# Solar_5_cell_V4_fixed_footprint.net
KiCad netlist of a schematic drawn in EAGLE
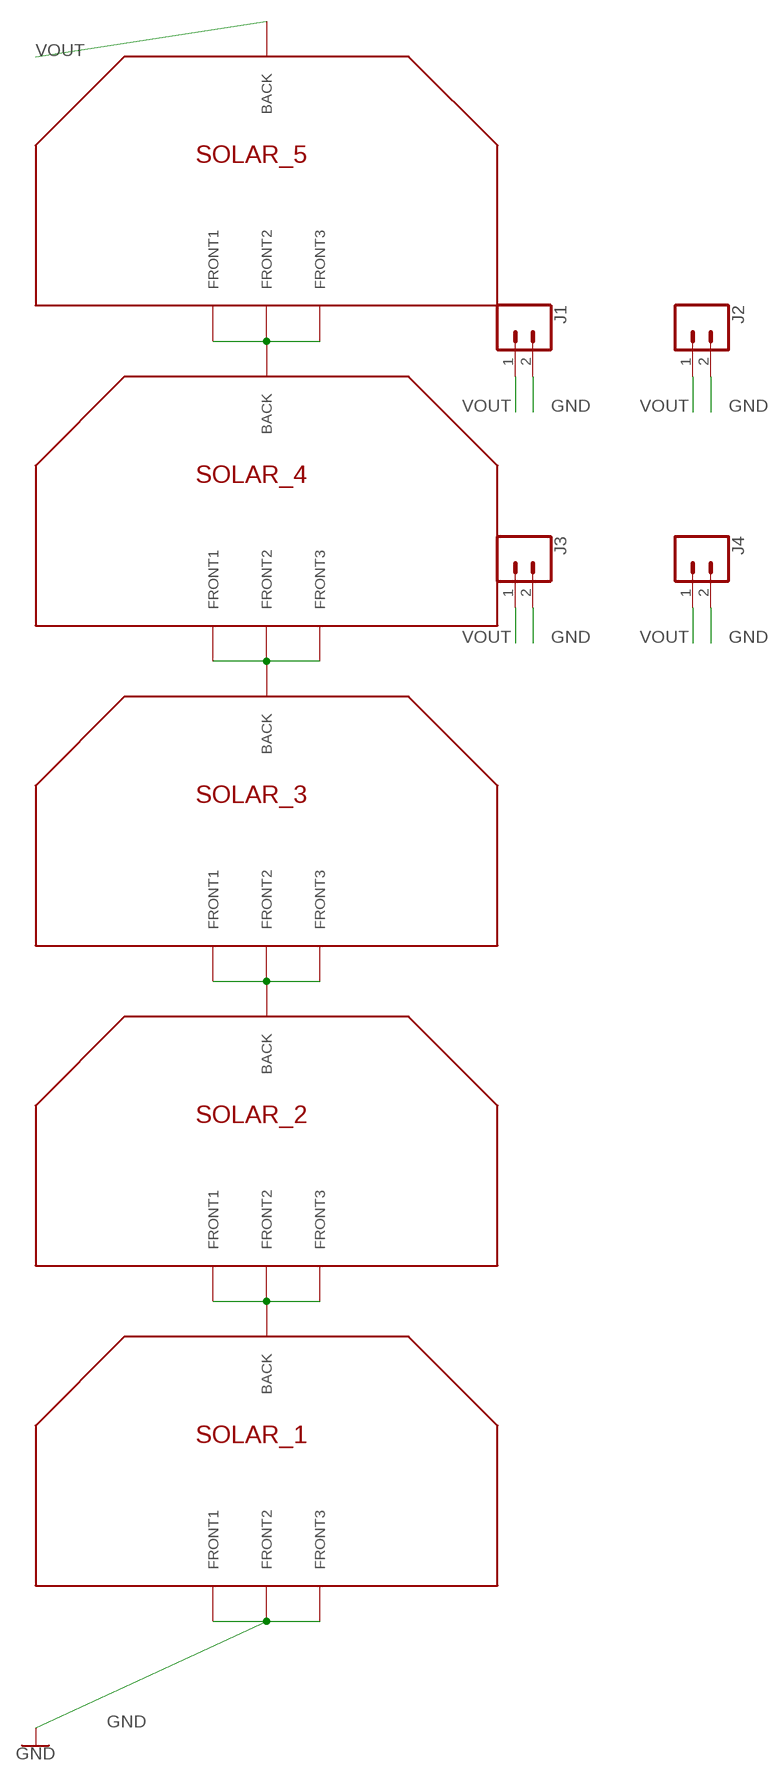
[diagram p0: schematic, sheet 1]

(export (version "E")
  (design (tool "Eeschema 10.0.6"))
  (components
    (comp (ref "J1")
      (value "CONN_02")
      (footprint "eagle-import:1X02")
      (libsource (lib "eagle-import") (part "CONN_02"))
    )
    (comp (ref "J2")
      (value "CONN_02")
      (footprint "eagle-import:1X02")
      (libsource (lib "eagle-import") (part "CONN_02"))
    )
    (comp (ref "J3")
      (value "CONN_02")
      (footprint "eagle-import:1X02")
      (libsource (lib "eagle-import") (part "CONN_02"))
    )
    (comp (ref "J4")
      (value "CONN_02")
      (footprint "eagle-import:1X02")
      (libsource (lib "eagle-import") (part "CONN_02"))
    )
    (comp (ref "SOLAR_1")
      (value "SOLAR_CELL_HALF_TABSFULL_TABS")
      (footprint "eagle-import:SOLAR_CELL_3G30A_FULL_TABS")
      (libsource (lib "eagle-import") (part "SOLAR_CELL_HALF_TABSFULL_TABS"))
    )
    (comp (ref "SOLAR_2")
      (value "SOLAR_CELL_HALF_TABSFULL_TABS")
      (footprint "eagle-import:SOLAR_CELL_3G30A_FULL_TABS")
      (libsource (lib "eagle-import") (part "SOLAR_CELL_HALF_TABSFULL_TABS"))
    )
    (comp (ref "SOLAR_3")
      (value "SOLAR_CELL_HALF_TABSFULL_TABS")
      (footprint "eagle-import:SOLAR_CELL_3G30A_FULL_TABS")
      (libsource (lib "eagle-import") (part "SOLAR_CELL_HALF_TABSFULL_TABS"))
    )
    (comp (ref "SOLAR_4")
      (value "SOLAR_CELL_HALF_TABSFULL_TABS")
      (footprint "eagle-import:SOLAR_CELL_3G30A_FULL_TABS")
      (libsource (lib "eagle-import") (part "SOLAR_CELL_HALF_TABSFULL_TABS"))
    )
    (comp (ref "SOLAR_5")
      (value "SOLAR_CELL_HALF_TABSFULL_TABS")
      (footprint "eagle-import:SOLAR_CELL_3G30A_FULL_TABS")
      (libsource (lib "eagle-import") (part "SOLAR_CELL_HALF_TABSFULL_TABS"))
    )
  )
  (nets
    (net (code "1") (name "/VOUT") (class "Default")
      (node (ref "J1") (pin "1") (pinfunction "1_1") (pintype "passive"))
      (node (ref "J2") (pin "1") (pinfunction "1_1") (pintype "passive"))
      (node (ref "J3") (pin "1") (pinfunction "1_1") (pintype "passive"))
      (node (ref "J4") (pin "1") (pinfunction "1_1") (pintype "passive"))
      (node (ref "SOLAR_5") (pin "P$1") (pinfunction "BACK_P$1") (pintype "bidirectional"))
    )
    (net (code "2") (name "GND") (class "Default")
      (node (ref "J1") (pin "2") (pinfunction "2_2") (pintype "passive"))
      (node (ref "J2") (pin "2") (pinfunction "2_2") (pintype "passive"))
      (node (ref "J3") (pin "2") (pinfunction "2_2") (pintype "passive"))
      (node (ref "J4") (pin "2") (pinfunction "2_2") (pintype "passive"))
      (node (ref "SOLAR_1") (pin "P$F1") (pinfunction "FRONT1_P$F1") (pintype "bidirectional"))
      (node (ref "SOLAR_1") (pin "P$F2") (pinfunction "FRONT2_P$F2") (pintype "bidirectional"))
      (node (ref "SOLAR_1") (pin "P$F3") (pinfunction "FRONT3_P$F3") (pintype "bidirectional"))
    )
    (net (code "3") (name "Net-(SOLAR_1-BACK)") (class "Default")
      (node (ref "SOLAR_1") (pin "P$1") (pinfunction "BACK_P$1") (pintype "bidirectional"))
      (node (ref "SOLAR_2") (pin "P$F1") (pinfunction "FRONT1_P$F1") (pintype "bidirectional"))
      (node (ref "SOLAR_2") (pin "P$F2") (pinfunction "FRONT2_P$F2") (pintype "bidirectional"))
      (node (ref "SOLAR_2") (pin "P$F3") (pinfunction "FRONT3_P$F3") (pintype "bidirectional"))
    )
    (net (code "4") (name "Net-(SOLAR_2-BACK)") (class "Default")
      (node (ref "SOLAR_2") (pin "P$1") (pinfunction "BACK_P$1") (pintype "bidirectional"))
      (node (ref "SOLAR_3") (pin "P$F1") (pinfunction "FRONT1_P$F1") (pintype "bidirectional"))
      (node (ref "SOLAR_3") (pin "P$F2") (pinfunction "FRONT2_P$F2") (pintype "bidirectional"))
      (node (ref "SOLAR_3") (pin "P$F3") (pinfunction "FRONT3_P$F3") (pintype "bidirectional"))
    )
    (net (code "5") (name "Net-(SOLAR_3-BACK)") (class "Default")
      (node (ref "SOLAR_3") (pin "P$1") (pinfunction "BACK_P$1") (pintype "bidirectional"))
      (node (ref "SOLAR_4") (pin "P$F1") (pinfunction "FRONT1_P$F1") (pintype "bidirectional"))
      (node (ref "SOLAR_4") (pin "P$F2") (pinfunction "FRONT2_P$F2") (pintype "bidirectional"))
      (node (ref "SOLAR_4") (pin "P$F3") (pinfunction "FRONT3_P$F3") (pintype "bidirectional"))
    )
    (net (code "6") (name "Net-(SOLAR_4-BACK)") (class "Default")
      (node (ref "SOLAR_4") (pin "P$1") (pinfunction "BACK_P$1") (pintype "bidirectional"))
      (node (ref "SOLAR_5") (pin "P$F1") (pinfunction "FRONT1_P$F1") (pintype "bidirectional"))
      (node (ref "SOLAR_5") (pin "P$F2") (pinfunction "FRONT2_P$F2") (pintype "bidirectional"))
      (node (ref "SOLAR_5") (pin "P$F3") (pinfunction "FRONT3_P$F3") (pintype "bidirectional"))
    )
  )
)
